# Timelapse_camera_RevC.net
KiCad netlist of a schematic drawn in EAGLE
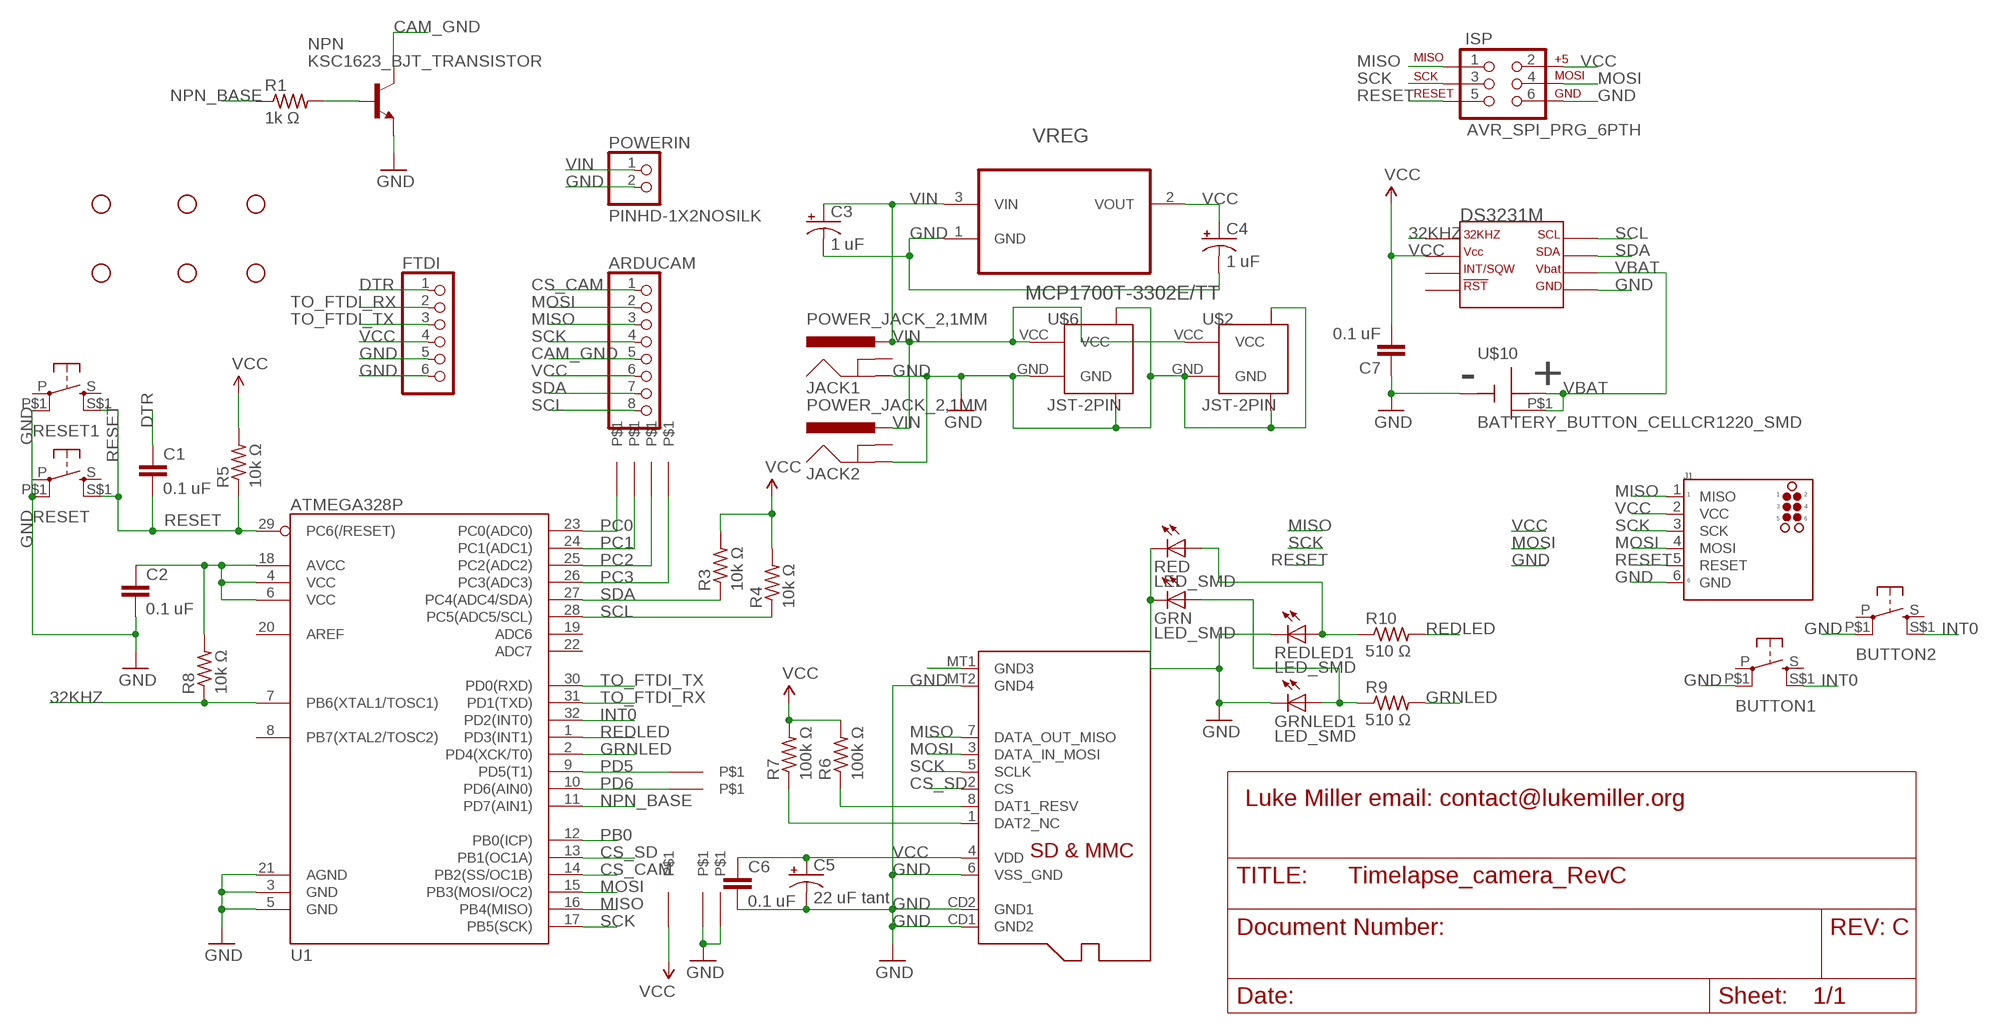
[diagram p0: schematic, sheet 1]

(export (version "E")
  (design (tool "Eeschema 10.0.6"))
  (components
    (comp (ref "ARDUCAM")
      (value "PINHD-1X8RIGHTANGLE_FEMALE")
      (footprint "eagle-import:1X08-RA")
      (libsource (lib "eagle-import") (part "PINHD-1X8RIGHTANGLE_FEMALE"))
    )
    (comp (ref "BUTTON1")
      (value "PUSHBUTTON_DPST_SMDSTANDARD")
      (footprint "eagle-import:PUSHBUTTON_DPST_SMD")
      (libsource (lib "eagle-import") (part "PUSHBUTTON_DPST_SMDSTANDARD"))
    )
    (comp (ref "BUTTON2")
      (value "PUSHBUTTON_DPST_SMDSTANDARD")
      (footprint "eagle-import:PUSHBUTTON_DPST_SMD")
      (libsource (lib "eagle-import") (part "PUSHBUTTON_DPST_SMDSTANDARD"))
    )
    (comp (ref "C1")
      (value "0.1 uF")
      (footprint "eagle-import:0805")
      (libsource (lib "eagle-import") (part "CAP0805"))
    )
    (comp (ref "C2")
      (value "0.1 uF")
      (footprint "eagle-import:0805")
      (libsource (lib "eagle-import") (part "CAP0805"))
    )
    (comp (ref "C3")
      (value "1 uF")
      (footprint "eagle-import:PANASONIC_B")
      (libsource (lib "eagle-import") (part "CPOL-USB"))
    )
    (comp (ref "C4")
      (value "1 uF")
      (footprint "eagle-import:PANASONIC_B")
      (libsource (lib "eagle-import") (part "CPOL-USB"))
    )
    (comp (ref "C5")
      (value "22 uF tant")
      (footprint "eagle-import:C0805_POL")
      (libsource (lib "eagle-import") (part "CPOL-US0805"))
    )
    (comp (ref "C6")
      (value "0.1 uF")
      (footprint "eagle-import:0805")
      (libsource (lib "eagle-import") (part "CAP0805"))
    )
    (comp (ref "C7")
      (value "0.1 uF")
      (footprint "eagle-import:0805")
      (libsource (lib "eagle-import") (part "CAP0805"))
    )
    (comp (ref "DS3231M")
      (value "DS3231MSOIC-8")
      (footprint "eagle-import:DS3231M_SOIC8")
      (libsource (lib "eagle-import") (part "DS3231MSOIC-8"))
    )
    (comp (ref "FTDI")
      (value "PINHD-1X6CB")
      (footprint "eagle-import:1X06-CLEANBIG")
      (libsource (lib "eagle-import") (part "PINHD-1X6CB"))
    )
    (comp (ref "GRN")
      (value "LED_SMD")
      (footprint "eagle-import:CHIPLED_0805")
      (libsource (lib "eagle-import") (part "LED_SMD"))
    )
    (comp (ref "GRNLED1")
      (value "LED_SMD")
      (footprint "eagle-import:CHIPLED_0805")
      (libsource (lib "eagle-import") (part "LED_SMD"))
    )
    (comp (ref "ISP")
      (value "AVR_SPI_PRG_6PTH")
      (footprint "eagle-import:2X3")
      (libsource (lib "eagle-import") (part "AVR_SPI_PRG_6PTH"))
    )
    (comp (ref "J1")
      (value "TC2030-MCP-NL")
      (footprint "eagle-import:TC2030-MCP-NL")
      (libsource (lib "eagle-import") (part "TC2030-MCP-NL"))
    )
    (comp (ref "JACK1")
      (value "POWER_JACK_2,1MM")
      (footprint "eagle-import:POWER_JACK_DC_2,1MM")
      (libsource (lib "eagle-import") (part "POWER_JACK_2,1MM"))
    )
    (comp (ref "JACK2")
      (value "POWER_JACK_2,1MM")
      (footprint "eagle-import:POWER_JACK_DC_2,1MM")
      (libsource (lib "eagle-import") (part "POWER_JACK_2,1MM"))
    )
    (comp (ref "NPN")
      (value "KSC1623_BJT_TRANSISTOR")
      (footprint "eagle-import:SOT23")
      (libsource (lib "eagle-import") (part "KSC1623_BJT_TRANSISTOR"))
    )
    (comp (ref "POWERIN")
      (value "PINHD-1X2NOSILK")
      (footprint "eagle-import:1X02_NOSILK")
      (libsource (lib "eagle-import") (part "PINHD-1X2NOSILK"))
    )
    (comp (ref "R1")
      (value "1k Ω")
      (footprint "eagle-import:R0805")
      (libsource (lib "eagle-import") (part "RESISTOR_SMDR0805"))
    )
    (comp (ref "R3")
      (value "10k Ω")
      (footprint "eagle-import:R0805")
      (libsource (lib "eagle-import") (part "RESISTOR_SMDR0805"))
    )
    (comp (ref "R4")
      (value "10k Ω")
      (footprint "eagle-import:R0805")
      (libsource (lib "eagle-import") (part "RESISTOR_SMDR0805"))
    )
    (comp (ref "R5")
      (value "10k Ω")
      (footprint "eagle-import:R0805")
      (libsource (lib "eagle-import") (part "RESISTOR_SMDR0805"))
    )
    (comp (ref "R6")
      (value "100k Ω")
      (footprint "eagle-import:R0805")
      (libsource (lib "eagle-import") (part "RESISTOR_SMDR0805"))
    )
    (comp (ref "R7")
      (value "100k Ω")
      (footprint "eagle-import:R0805")
      (libsource (lib "eagle-import") (part "RESISTOR_SMDR0805"))
    )
    (comp (ref "R8")
      (value "10k Ω")
      (footprint "eagle-import:R0805")
      (libsource (lib "eagle-import") (part "RESISTOR_SMDR0805"))
    )
    (comp (ref "R9")
      (value "510 Ω")
      (footprint "eagle-import:R0805")
      (libsource (lib "eagle-import") (part "RESISTOR_SMDR0805"))
    )
    (comp (ref "R10")
      (value "510 Ω")
      (footprint "eagle-import:R0805")
      (libsource (lib "eagle-import") (part "RESISTOR_SMDR0805"))
    )
    (comp (ref "RED")
      (value "LED_SMD")
      (footprint "eagle-import:CHIPLED_0805")
      (libsource (lib "eagle-import") (part "LED_SMD"))
    )
    (comp (ref "REDLED1")
      (value "LED_SMD")
      (footprint "eagle-import:CHIPLED_0805")
      (libsource (lib "eagle-import") (part "LED_SMD"))
    )
    (comp (ref "RESET")
      (value "PUSHBUTTON_DPST_SMDSTANDARD")
      (footprint "eagle-import:PUSHBUTTON_DPST_SMD")
      (libsource (lib "eagle-import") (part "PUSHBUTTON_DPST_SMDSTANDARD"))
    )
    (comp (ref "RESET1")
      (value "PUSHBUTTON_DPST_SMDSTANDARD")
      (footprint "eagle-import:PUSHBUTTON_DPST_SMD")
      (libsource (lib "eagle-import") (part "PUSHBUTTON_DPST_SMDSTANDARD"))
    )
    (comp (ref "STANDOFF1")
      (value "STAND-OFF")
      (footprint "eagle-import:STAND-OFF")
      (libsource (lib "eagle-import") (part "STAND-OFF"))
    )
    (comp (ref "STANDOFF2")
      (value "STAND-OFF")
      (footprint "eagle-import:STAND-OFF")
      (libsource (lib "eagle-import") (part "STAND-OFF"))
    )
    (comp (ref "STANDOFF3")
      (value "STAND-OFF")
      (footprint "eagle-import:STAND-OFF")
      (libsource (lib "eagle-import") (part "STAND-OFF"))
    )
    (comp (ref "STANDOFF4")
      (value "STAND-OFF")
      (footprint "eagle-import:STAND-OFF")
      (libsource (lib "eagle-import") (part "STAND-OFF"))
    )
    (comp (ref "STANDOFF5")
      (value "STAND-OFF")
      (footprint "eagle-import:STAND-OFF")
      (libsource (lib "eagle-import") (part "STAND-OFF"))
    )
    (comp (ref "STANDOFF6")
      (value "STAND-OFF")
      (footprint "eagle-import:STAND-OFF")
      (libsource (lib "eagle-import") (part "STAND-OFF"))
    )
    (comp (ref "U$1")
      (value "PINHD-1X1STANDARD")
      (footprint "eagle-import:1X01")
      (libsource (lib "eagle-import") (part "PINHD-1X1STANDARD"))
    )
    (comp (ref "U$2")
      (value "JST-2PIN")
      (footprint "eagle-import:JST-2-SMD-VERT")
      (libsource (lib "eagle-import") (part "JST-2PIN"))
    )
    (comp (ref "U$3")
      (value "MICROSD")
      (footprint "eagle-import:MICROSD")
      (libsource (lib "eagle-import") (part "MICROSD"))
    )
    (comp (ref "U$4")
      (value "PINHD-1X1STANDARD")
      (footprint "eagle-import:1X01")
      (libsource (lib "eagle-import") (part "PINHD-1X1STANDARD"))
    )
    (comp (ref "U$6")
      (value "JST-2PIN")
      (footprint "eagle-import:JST-2-SMD-VERT")
      (libsource (lib "eagle-import") (part "JST-2PIN"))
    )
    (comp (ref "U$7")
      (value "PINHD-1X1STANDARD")
      (footprint "eagle-import:1X01")
      (libsource (lib "eagle-import") (part "PINHD-1X1STANDARD"))
    )
    (comp (ref "U$8")
      (value "PINHD-1X1STANDARD")
      (footprint "eagle-import:1X01")
      (libsource (lib "eagle-import") (part "PINHD-1X1STANDARD"))
    )
    (comp (ref "U$9")
      (value "PINHD-1X1STANDARD")
      (footprint "eagle-import:1X01")
      (libsource (lib "eagle-import") (part "PINHD-1X1STANDARD"))
    )
    (comp (ref "U$10")
      (value "BATTERY_BUTTON_CELLCR1220_SMD")
      (footprint "eagle-import:CR1220_BATTERY_HOLDER_SMD")
      (libsource (lib "eagle-import") (part "BATTERY_BUTTON_CELLCR1220_SMD"))
    )
    (comp (ref "U$11")
      (value "PINHD-1X1STANDARD")
      (footprint "eagle-import:1X01")
      (libsource (lib "eagle-import") (part "PINHD-1X1STANDARD"))
    )
    (comp (ref "U$12")
      (value "PINHD-1X1STANDARD")
      (footprint "eagle-import:1X01")
      (libsource (lib "eagle-import") (part "PINHD-1X1STANDARD"))
    )
    (comp (ref "U$13")
      (value "PINHD-1X1STANDARD")
      (footprint "eagle-import:1X01")
      (libsource (lib "eagle-import") (part "PINHD-1X1STANDARD"))
    )
    (comp (ref "U$14")
      (value "PINHD-1X1STANDARD")
      (footprint "eagle-import:1X01")
      (libsource (lib "eagle-import") (part "PINHD-1X1STANDARD"))
    )
    (comp (ref "U1")
      (value "ATMEGA328P")
      (footprint "eagle-import:TQFP32-08")
      (libsource (lib "eagle-import") (part "ATMEGA328_SMT"))
    )
    (comp (ref "VREG")
      (value "MCP1700T-3302E/TT")
      (footprint "eagle-import:SOT95P237X112-3N")
      (libsource (lib "eagle-import") (part "MCP1700T-3302E/TT"))
    )
  )
  (nets
    (net (code "1") (name "/32KHZ") (class "Default")
      (node (ref "DS3231M") (pin "1") (pinfunction "P$1_32KHZ_1") (pintype "bidirectional"))
      (node (ref "R8") (pin "1") (pinfunction "1_1") (pintype "passive"))
      (node (ref "U1") (pin "7") (pinfunction "PB6(XTAL1/TOSC1)_7") (pintype "bidirectional"))
    )
    (net (code "2") (name "/CAM_GND") (class "Default")
      (node (ref "ARDUCAM") (pin "5") (pinfunction "5_5") (pintype "passive"))
      (node (ref "NPN") (pin "3") (pinfunction "C_3") (pintype "passive"))
    )
    (net (code "3") (name "/CS_CAM") (class "Default")
      (node (ref "ARDUCAM") (pin "1") (pinfunction "1_1") (pintype "passive"))
      (node (ref "U1") (pin "14") (pinfunction "PB2(SS/OC1B)_14") (pintype "bidirectional"))
    )
    (net (code "4") (name "/CS_SD") (class "Default")
      (node (ref "U$3") (pin "2") (pinfunction "CS_2") (pintype "input"))
      (node (ref "U1") (pin "13") (pinfunction "PB1(OC1A)_13") (pintype "bidirectional"))
    )
    (net (code "5") (name "/DTR") (class "Default")
      (node (ref "C1") (pin "1") (pinfunction "1_1") (pintype "passive"))
      (node (ref "FTDI") (pin "1") (pinfunction "1_1") (pintype "passive"))
    )
    (net (code "6") (name "/GRNLED") (class "Default")
      (node (ref "R9") (pin "2") (pinfunction "2_2") (pintype "passive"))
      (node (ref "U1") (pin "2") (pinfunction "PD4(XCK/T0)_2") (pintype "bidirectional"))
    )
    (net (code "7") (name "/INT0") (class "Default")
      (node (ref "BUTTON1") (pin "S$1") (pinfunction "S1_S$1") (pintype "passive"))
      (node (ref "BUTTON2") (pin "S$1") (pinfunction "S1_S$1") (pintype "passive"))
      (node (ref "U1") (pin "32") (pinfunction "PD2(INT0)_32") (pintype "bidirectional"))
    )
    (net (code "8") (name "/MISO") (class "Default")
      (node (ref "ARDUCAM") (pin "3") (pinfunction "3_3") (pintype "passive"))
      (node (ref "ISP") (pin "1") (pinfunction "1_1") (pintype "passive"))
      (node (ref "J1") (pin "1") (pinfunction "MISO_1") (pintype "bidirectional"))
      (node (ref "U$3") (pin "7") (pinfunction "DATA_OUT_MISO_7") (pintype "output"))
      (node (ref "U1") (pin "16") (pinfunction "PB4(MISO)_16") (pintype "bidirectional"))
    )
    (net (code "9") (name "/MOSI") (class "Default")
      (node (ref "ARDUCAM") (pin "2") (pinfunction "2_2") (pintype "passive"))
      (node (ref "ISP") (pin "4") (pinfunction "4_4") (pintype "passive"))
      (node (ref "J1") (pin "4") (pinfunction "MOSI_4") (pintype "bidirectional"))
      (node (ref "U$3") (pin "3") (pinfunction "DATA_IN_MOSI_3") (pintype "input"))
      (node (ref "U1") (pin "15") (pinfunction "PB3(MOSI/OC2)_15") (pintype "bidirectional"))
    )
    (net (code "10") (name "/NPN_BASE") (class "Default")
      (node (ref "R1") (pin "1") (pinfunction "1_1") (pintype "passive"))
      (node (ref "U1") (pin "11") (pinfunction "PD7(AIN1)_11") (pintype "bidirectional"))
    )
    (net (code "11") (name "/PB0") (class "Default")
      (node (ref "U1") (pin "12") (pinfunction "PB0(ICP)_12") (pintype "bidirectional"))
    )
    (net (code "12") (name "/PC0") (class "Default")
      (node (ref "U$1") (pin "1") (pinfunction "P$1_1") (pintype "bidirectional"))
      (node (ref "U1") (pin "23") (pinfunction "PC0(ADC0)_23") (pintype "bidirectional"))
    )
    (net (code "13") (name "/PC1") (class "Default")
      (node (ref "U$4") (pin "1") (pinfunction "P$1_1") (pintype "bidirectional"))
      (node (ref "U1") (pin "24") (pinfunction "PC1(ADC1)_24") (pintype "bidirectional"))
    )
    (net (code "14") (name "/PC2") (class "Default")
      (node (ref "U$7") (pin "1") (pinfunction "P$1_1") (pintype "bidirectional"))
      (node (ref "U1") (pin "25") (pinfunction "PC2(ADC2)_25") (pintype "bidirectional"))
    )
    (net (code "15") (name "/PC3") (class "Default")
      (node (ref "U$8") (pin "1") (pinfunction "P$1_1") (pintype "bidirectional"))
      (node (ref "U1") (pin "26") (pinfunction "PC3(ADC3)_26") (pintype "bidirectional"))
    )
    (net (code "16") (name "/PD5") (class "Default")
      (node (ref "U$9") (pin "1") (pinfunction "P$1_1") (pintype "bidirectional"))
      (node (ref "U1") (pin "9") (pinfunction "PD5(T1)_9") (pintype "bidirectional"))
    )
    (net (code "17") (name "/PD6") (class "Default")
      (node (ref "U$11") (pin "1") (pinfunction "P$1_1") (pintype "bidirectional"))
      (node (ref "U1") (pin "10") (pinfunction "PD6(AIN0)_10") (pintype "bidirectional"))
    )
    (net (code "18") (name "/REDLED") (class "Default")
      (node (ref "R10") (pin "2") (pinfunction "2_2") (pintype "passive"))
      (node (ref "U1") (pin "1") (pinfunction "PD3(INT1)_1") (pintype "bidirectional"))
    )
    (net (code "19") (name "/RESET") (class "Default")
      (node (ref "C1") (pin "2") (pinfunction "2_2") (pintype "passive"))
      (node (ref "ISP") (pin "5") (pinfunction "5_5") (pintype "passive"))
      (node (ref "J1") (pin "5") (pinfunction "RESET_5") (pintype "bidirectional"))
      (node (ref "R5") (pin "1") (pinfunction "1_1") (pintype "passive"))
      (node (ref "RESET") (pin "S$1") (pinfunction "S1_S$1") (pintype "passive"))
      (node (ref "RESET1") (pin "S$1") (pinfunction "S1_S$1") (pintype "passive"))
      (node (ref "U1") (pin "29") (pinfunction "PC6(/RESET)_29") (pintype "bidirectional"))
    )
    (net (code "20") (name "/SCK") (class "Default")
      (node (ref "ARDUCAM") (pin "4") (pinfunction "4_4") (pintype "passive"))
      (node (ref "ISP") (pin "3") (pinfunction "3_3") (pintype "passive"))
      (node (ref "J1") (pin "3") (pinfunction "SCK_3") (pintype "bidirectional"))
      (node (ref "U$3") (pin "5") (pinfunction "SCLK_5") (pintype "input"))
      (node (ref "U1") (pin "17") (pinfunction "PB5(SCK)_17") (pintype "bidirectional"))
    )
    (net (code "21") (name "/SCL") (class "Default")
      (node (ref "ARDUCAM") (pin "8") (pinfunction "8_8") (pintype "passive"))
      (node (ref "DS3231M") (pin "8") (pinfunction "P$8_SCL_8") (pintype "bidirectional"))
      (node (ref "R4") (pin "1") (pinfunction "1_1") (pintype "passive"))
      (node (ref "U1") (pin "28") (pinfunction "PC5(ADC5/SCL)_28") (pintype "bidirectional"))
    )
    (net (code "22") (name "/SDA") (class "Default")
      (node (ref "ARDUCAM") (pin "7") (pinfunction "7_7") (pintype "passive"))
      (node (ref "DS3231M") (pin "7") (pinfunction "P$7_SDA_7") (pintype "bidirectional"))
      (node (ref "R3") (pin "1") (pinfunction "1_1") (pintype "passive"))
      (node (ref "U1") (pin "27") (pinfunction "PC4(ADC4/SDA)_27") (pintype "bidirectional"))
    )
    (net (code "23") (name "/TO_FTDI_RX") (class "Default")
      (node (ref "FTDI") (pin "2") (pinfunction "2_2") (pintype "passive"))
      (node (ref "U1") (pin "31") (pinfunction "PD1(TXD)_31") (pintype "bidirectional"))
    )
    (net (code "24") (name "/TO_FTDI_TX") (class "Default")
      (node (ref "FTDI") (pin "3") (pinfunction "3_3") (pintype "passive"))
      (node (ref "U1") (pin "30") (pinfunction "PD0(RXD)_30") (pintype "bidirectional"))
    )
    (net (code "25") (name "/VBAT") (class "Default")
      (node (ref "DS3231M") (pin "6") (pinfunction "P$6_VBAT_6") (pintype "bidirectional"))
      (node (ref "U$10") (pin "P$1") (pinfunction "P$2_VBAT_P$1") (pintype "power_in"))
      (node (ref "U$10") (pin "P$2") (pinfunction "VBAT_P$2") (pintype "power_in"))
    )
    (net (code "26") (name "/VIN") (class "Default")
      (node (ref "C3") (pin "+") (pinfunction "+_+") (pintype "passive"))
      (node (ref "JACK1") (pin "P$1") (pinfunction "PWR_P$1") (pintype "bidirectional"))
      (node (ref "JACK2") (pin "P$1") (pinfunction "PWR_P$1") (pintype "bidirectional"))
      (node (ref "POWERIN") (pin "1") (pinfunction "1_1") (pintype "passive"))
      (node (ref "U$2") (pin "VCC") (pinfunction "VCC_VCC") (pintype "power_in"))
      (node (ref "U$6") (pin "VCC") (pinfunction "VCC_VCC") (pintype "power_in"))
      (node (ref "VREG") (pin "3") (pinfunction "VIN_3") (pintype "input"))
    )
    (net (code "27") (name "GND") (class "Default")
      (node (ref "BUTTON1") (pin "P$1") (pinfunction "P1_P$1") (pintype "passive"))
      (node (ref "BUTTON2") (pin "P$1") (pinfunction "P1_P$1") (pintype "passive"))
      (node (ref "C2") (pin "2") (pinfunction "2_2") (pintype "passive"))
      (node (ref "C3") (pin "-") (pinfunction "-_-") (pintype "passive"))
      (node (ref "C4") (pin "-") (pinfunction "-_-") (pintype "passive"))
      (node (ref "C5") (pin "P$2_C") (pinfunction "-_P$2_C") (pintype "passive"))
      (node (ref "C6") (pin "2") (pinfunction "2_2") (pintype "passive"))
      (node (ref "C7") (pin "1") (pinfunction "1_1") (pintype "passive"))
      (node (ref "DS3231M") (pin "5") (pinfunction "P$5_GND_5") (pintype "power_in"))
      (node (ref "FTDI") (pin "5") (pinfunction "5_5") (pintype "passive"))
      (node (ref "FTDI") (pin "6") (pinfunction "6_6") (pintype "passive"))
      (node (ref "GRN") (pin "C") (pinfunction "C_C") (pintype "passive"))
      (node (ref "GRNLED1") (pin "C") (pinfunction "C_C") (pintype "passive"))
      (node (ref "ISP") (pin "6") (pinfunction "6_6") (pintype "passive"))
      (node (ref "J1") (pin "6") (pinfunction "GND_6") (pintype "power_in"))
      (node (ref "JACK1") (pin "P$2") (pinfunction "GND_P$2") (pintype "bidirectional"))
      (node (ref "JACK2") (pin "P$2") (pinfunction "GND_P$2") (pintype "bidirectional"))
      (node (ref "NPN") (pin "2") (pinfunction "E_2") (pintype "passive"))
      (node (ref "POWERIN") (pin "2") (pinfunction "2_2") (pintype "passive"))
      (node (ref "RED") (pin "C") (pinfunction "C_C") (pintype "passive"))
      (node (ref "REDLED1") (pin "C") (pinfunction "C_C") (pintype "passive"))
      (node (ref "RESET") (pin "P$1") (pinfunction "P1_P$1") (pintype "passive"))
      (node (ref "RESET1") (pin "P$1") (pinfunction "P1_P$1") (pintype "passive"))
      (node (ref "U$10") (pin "GND") (pinfunction "GND_GND") (pintype "power_in"))
      (node (ref "U$12") (pin "1") (pinfunction "P$1_1") (pintype "bidirectional"))
      (node (ref "U$14") (pin "1") (pinfunction "P$1_1") (pintype "bidirectional"))
      (node (ref "U$2") (pin "GND") (pinfunction "GND_GND") (pintype "power_in"))
      (node (ref "U$2") (pin "P$1") (pinfunction "BODY1_P$1") (pintype "power_in"))
      (node (ref "U$2") (pin "P$2") (pinfunction "BODY2_P$2") (pintype "power_in"))
      (node (ref "U$3") (pin "6") (pinfunction "VSS_GND_6") (pintype "power_in"))
      (node (ref "U$3") (pin "CD1") (pinfunction "GND2_CD1") (pintype "power_in"))
      (node (ref "U$3") (pin "CD2") (pinfunction "GND1_CD2") (pintype "power_in"))
      (node (ref "U$3") (pin "MT2") (pinfunction "GND4_MT2") (pintype "passive"))
      (node (ref "U$6") (pin "GND") (pinfunction "GND_GND") (pintype "power_in"))
      (node (ref "U$6") (pin "P$1") (pinfunction "BODY1_P$1") (pintype "power_in"))
      (node (ref "U$6") (pin "P$2") (pinfunction "BODY2_P$2") (pintype "power_in"))
      (node (ref "U1") (pin "21") (pinfunction "AGND_21") (pintype "bidirectional"))
      (node (ref "U1") (pin "3") (pinfunction "GND_3") (pintype "bidirectional"))
      (node (ref "U1") (pin "5") (pinfunction "GND_5") (pintype "bidirectional"))
      (node (ref "VREG") (pin "1") (pinfunction "GND_1") (pintype "passive"))
    )
    (net (code "28") (name "Net-(GRN-PadA)") (class "Default")
      (node (ref "GRN") (pin "A") (pinfunction "A_A") (pintype "passive"))
      (node (ref "GRNLED1") (pin "A") (pinfunction "A_A") (pintype "passive"))
      (node (ref "R9") (pin "1") (pinfunction "1_1") (pintype "passive"))
    )
    (net (code "29") (name "Net-(NPN-B)") (class "Default")
      (node (ref "NPN") (pin "1") (pinfunction "B_1") (pintype "passive"))
      (node (ref "R1") (pin "2") (pinfunction "2_2") (pintype "passive"))
    )
    (net (code "30") (name "Net-(R10-Pad1)") (class "Default")
      (node (ref "R10") (pin "1") (pinfunction "1_1") (pintype "passive"))
      (node (ref "RED") (pin "A") (pinfunction "A_A") (pintype "passive"))
      (node (ref "REDLED1") (pin "A") (pinfunction "A_A") (pintype "passive"))
    )
    (net (code "31") (name "Net-(U$3-DAT1_RESV)") (class "Default")
      (node (ref "R6") (pin "1") (pinfunction "1_1") (pintype "passive"))
      (node (ref "U$3") (pin "8") (pinfunction "DAT1_RESV_8") (pintype "bidirectional"))
    )
    (net (code "32") (name "Net-(U$3-DAT2_NC)") (class "Default")
      (node (ref "R7") (pin "1") (pinfunction "1_1") (pintype "passive"))
      (node (ref "U$3") (pin "1") (pinfunction "DAT2_NC_1") (pintype "bidirectional"))
    )
    (net (code "33") (name "VCC") (class "Default")
      (node (ref "ARDUCAM") (pin "6") (pinfunction "6_6") (pintype "passive"))
      (node (ref "C2") (pin "1") (pinfunction "1_1") (pintype "passive"))
      (node (ref "C4") (pin "+") (pinfunction "+_+") (pintype "passive"))
      (node (ref "C5") (pin "P$1_A") (pinfunction "+_P$1_A") (pintype "passive"))
      (node (ref "C6") (pin "1") (pinfunction "1_1") (pintype "passive"))
      (node (ref "C7") (pin "2") (pinfunction "2_2") (pintype "passive"))
      (node (ref "DS3231M") (pin "2") (pinfunction "P$2_VCC_2") (pintype "power_in"))
      (node (ref "FTDI") (pin "4") (pinfunction "4_4") (pintype "passive"))
      (node (ref "ISP") (pin "2") (pinfunction "2_2") (pintype "passive"))
      (node (ref "J1") (pin "2") (pinfunction "VCC_2") (pintype "power_in"))
      (node (ref "R3") (pin "2") (pinfunction "2_2") (pintype "passive"))
      (node (ref "R4") (pin "2") (pinfunction "2_2") (pintype "passive"))
      (node (ref "R5") (pin "2") (pinfunction "2_2") (pintype "passive"))
      (node (ref "R6") (pin "2") (pinfunction "2_2") (pintype "passive"))
      (node (ref "R7") (pin "2") (pinfunction "2_2") (pintype "passive"))
      (node (ref "R8") (pin "2") (pinfunction "2_2") (pintype "passive"))
      (node (ref "U$13") (pin "1") (pinfunction "P$1_1") (pintype "bidirectional"))
      (node (ref "U$3") (pin "4") (pinfunction "VDD_4") (pintype "power_in"))
      (node (ref "U1") (pin "18") (pinfunction "AVCC_18") (pintype "bidirectional"))
      (node (ref "U1") (pin "4") (pinfunction "VCC_4") (pintype "bidirectional"))
      (node (ref "U1") (pin "6") (pinfunction "VCC_6") (pintype "bidirectional"))
      (node (ref "VREG") (pin "2") (pinfunction "VOUT_2") (pintype "output"))
    )
    (net (code "34") (name "unconnected-(BUTTON1-PadP)") (class "Default")
      (node (ref "BUTTON1") (pin "P") (pinfunction "P_P") (pintype "passive"))
    )
    (net (code "35") (name "unconnected-(BUTTON1-PadS)") (class "Default")
      (node (ref "BUTTON1") (pin "S") (pinfunction "S_S") (pintype "passive"))
    )
    (net (code "36") (name "unconnected-(BUTTON2-PadP)") (class "Default")
      (node (ref "BUTTON2") (pin "P") (pinfunction "P_P") (pintype "passive"))
    )
    (net (code "37") (name "unconnected-(BUTTON2-PadS)") (class "Default")
      (node (ref "BUTTON2") (pin "S") (pinfunction "S_S") (pintype "passive"))
    )
    (net (code "38") (name "unconnected-(DS3231M-P$3_INT-Pad3)") (class "Default")
      (node (ref "DS3231M") (pin "3") (pinfunction "P$3_INT_3") (pintype "bidirectional"))
    )
    (net (code "39") (name "unconnected-(DS3231M-P$4_RST-Pad4)") (class "Default")
      (node (ref "DS3231M") (pin "4") (pinfunction "P$4_RST_4") (pintype "bidirectional"))
    )
    (net (code "40") (name "unconnected-(JACK1-GNDBREAK-PadP$3)") (class "Default")
      (node (ref "JACK1") (pin "P$3") (pinfunction "GNDBREAK_P$3") (pintype "bidirectional"))
    )
    (net (code "41") (name "unconnected-(JACK2-GNDBREAK-PadP$3)") (class "Default")
      (node (ref "JACK2") (pin "P$3") (pinfunction "GNDBREAK_P$3") (pintype "bidirectional"))
    )
    (net (code "42") (name "unconnected-(RESET-PadP)") (class "Default")
      (node (ref "RESET") (pin "P") (pinfunction "P_P") (pintype "passive"))
    )
    (net (code "43") (name "unconnected-(RESET-PadS)") (class "Default")
      (node (ref "RESET") (pin "S") (pinfunction "S_S") (pintype "passive"))
    )
    (net (code "44") (name "unconnected-(RESET1-PadP)") (class "Default")
      (node (ref "RESET1") (pin "P") (pinfunction "P_P") (pintype "passive"))
    )
    (net (code "45") (name "unconnected-(RESET1-PadS)") (class "Default")
      (node (ref "RESET1") (pin "S") (pinfunction "S_S") (pintype "passive"))
    )
    (net (code "46") (name "unconnected-(U$3-GND3-PadMT1)") (class "Default")
      (node (ref "U$3") (pin "MT1") (pinfunction "GND3_MT1") (pintype "passive"))
    )
    (net (code "47") (name "unconnected-(U1-ADC6-Pad19)") (class "Default")
      (node (ref "U1") (pin "19") (pinfunction "ADC6_19") (pintype "bidirectional"))
    )
    (net (code "48") (name "unconnected-(U1-ADC7-Pad22)") (class "Default")
      (node (ref "U1") (pin "22") (pinfunction "ADC7_22") (pintype "bidirectional"))
    )
    (net (code "49") (name "unconnected-(U1-AREF-Pad20)") (class "Default")
      (node (ref "U1") (pin "20") (pinfunction "AREF_20") (pintype "bidirectional"))
    )
    (net (code "50") (name "unconnected-(U1-PB7(XTAL2{slash}TOSC2)-Pad8)") (class "Default")
      (node (ref "U1") (pin "8") (pinfunction "PB7(XTAL2/TOSC2)_8") (pintype "bidirectional"))
    )
  )
)
